# stm.net
KiCad netlist of a schematic drawn in Altium Designer
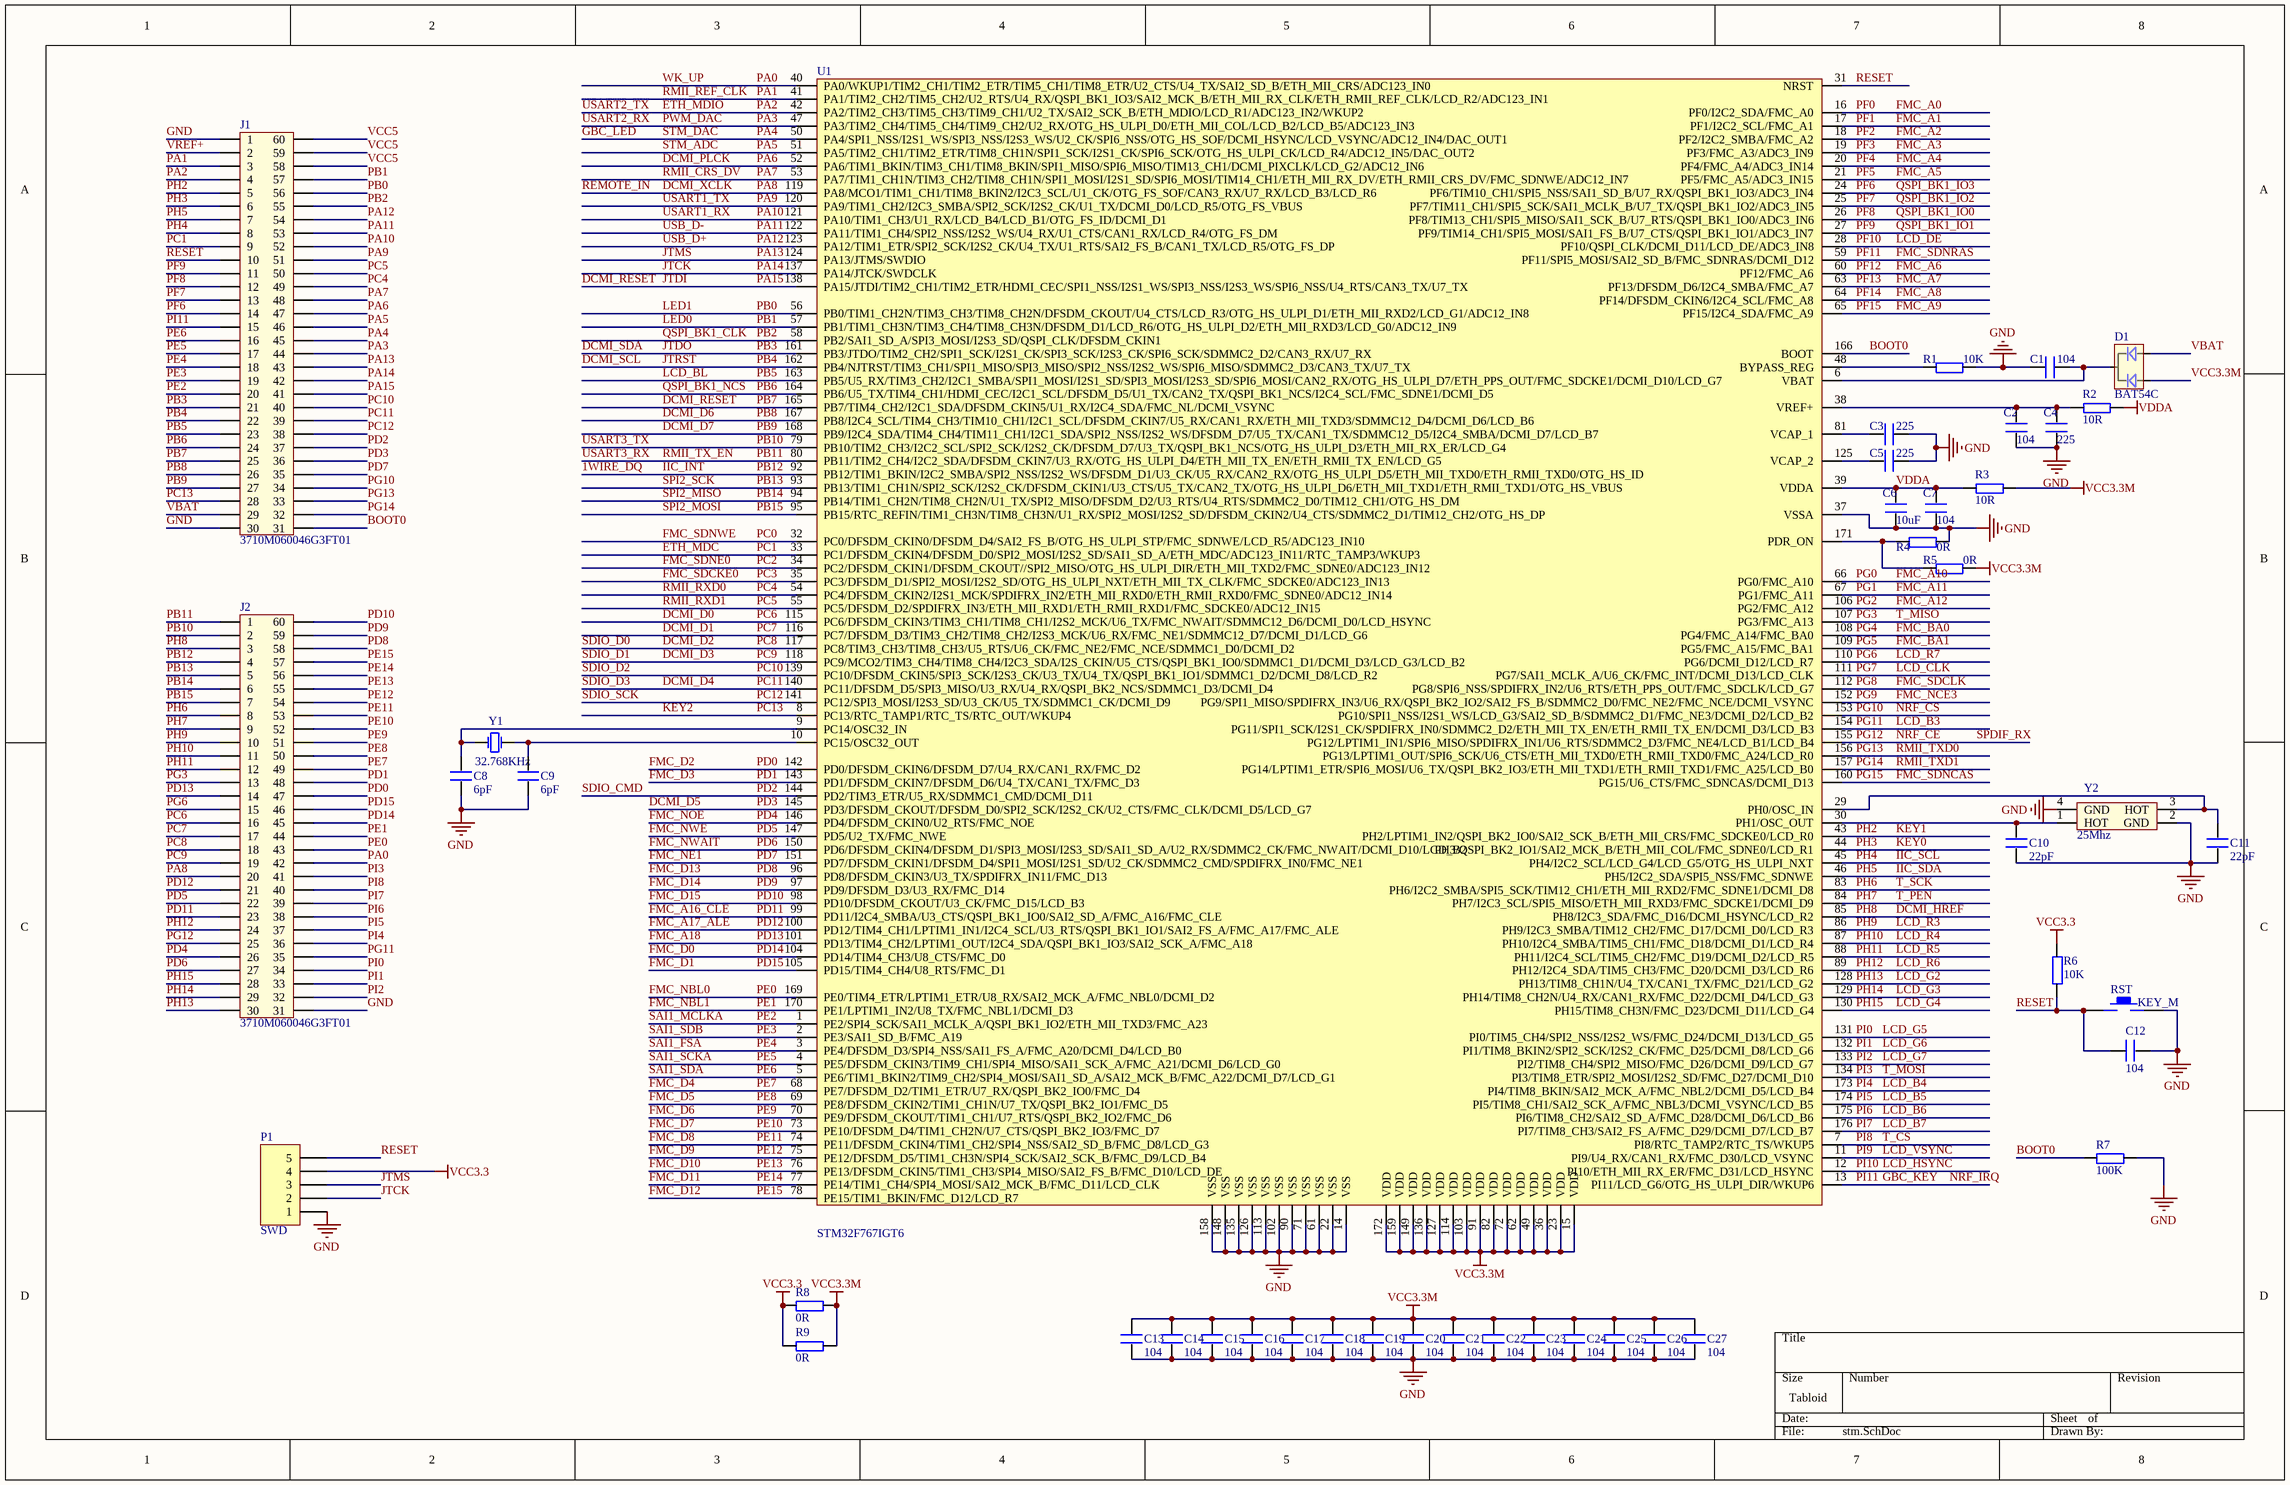
[diagram p0: stm.SchDoc]

(export (version "E")
  (design (tool "Eeschema 10.0.6"))
  (components
    (comp (ref "C1") (value "104") (footprint "0805") (libsource (lib "STM32F767核心板封装库") (part "C")))
    (comp (ref "C2") (value "104") (footprint "0805") (libsource (lib "STM32F767核心板封装库") (part "C")))
    (comp (ref "C3") (value "225") (footprint "0805") (libsource (lib "STM32F767核心板封装库") (part "C")))
    (comp (ref "C4") (value "225") (footprint "0805") (libsource (lib "STM32F767核心板封装库") (part "C")))
    (comp (ref "C5") (value "225") (footprint "0805") (libsource (lib "STM32F767核心板封装库") (part "C")))
    (comp (ref "C6") (value "10uF") (footprint "0805") (libsource (lib "STM32F767核心板封装库") (part "C")))
    (comp (ref "C7") (value "104") (footprint "0805") (libsource (lib "STM32F767核心板封装库") (part "C")))
    (comp (ref "C8") (value "6pF") (footprint "0805") (libsource (lib "STM32F767核心板封装库") (part "C")))
    (comp (ref "C9") (value "6pF") (footprint "0805") (libsource (lib "STM32F767核心板封装库") (part "C")))
    (comp (ref "C10") (value "22pF") (footprint "0805") (libsource (lib "STM32F767核心板封装库") (part "C")))
    (comp (ref "C11") (value "22pF") (footprint "0805") (libsource (lib "STM32F767核心板封装库") (part "C")))
    (comp (ref "C12") (value "104") (footprint "0805") (libsource (lib "STM32F767核心板封装库") (part "C")))
    (comp (ref "C13") (value "104") (footprint "0805") (libsource (lib "STM32F767核心板封装库") (part "C")))
    (comp (ref "C14") (value "104") (footprint "0805") (libsource (lib "STM32F767核心板封装库") (part "C")))
    (comp (ref "C15") (value "104") (footprint "0805") (libsource (lib "STM32F767核心板封装库") (part "C")))
    (comp (ref "C16") (value "104") (footprint "0805") (libsource (lib "STM32F767核心板封装库") (part "C")))
    (comp (ref "C17") (value "104") (footprint "0805") (libsource (lib "STM32F767核心板封装库") (part "C")))
    (comp (ref "C18") (value "104") (footprint "0805") (libsource (lib "STM32F767核心板封装库") (part "C")))
    (comp (ref "C19") (value "104") (footprint "0805") (libsource (lib "STM32F767核心板封装库") (part "C")))
    (comp (ref "C20") (value "104") (footprint "0805") (libsource (lib "STM32F767核心板封装库") (part "C")))
    (comp (ref "C21") (value "104") (footprint "0805") (libsource (lib "STM32F767核心板封装库") (part "C")))
    (comp (ref "C22") (value "104") (footprint "0805") (libsource (lib "STM32F767核心板封装库") (part "C")))
    (comp (ref "C23") (value "104") (footprint "0805") (libsource (lib "STM32F767核心板封装库") (part "C")))
    (comp (ref "C24") (value "104") (footprint "0805") (libsource (lib "STM32F767核心板封装库") (part "C")))
    (comp (ref "C25") (value "104") (footprint "0805") (libsource (lib "STM32F767核心板封装库") (part "C")))
    (comp (ref "C26") (value "104") (footprint "0805") (libsource (lib "STM32F767核心板封装库") (part "C")))
    (comp (ref "C27") (value "104") (footprint "0805") (libsource (lib "STM32F767核心板封装库") (part "C")))
    (comp (ref "D1")
      (value "BAT54C")
      (footprint "SOT-23")
      (description "双肖特基二极管")
      (libsource (lib "STM32F767核心板封装库") (part "BAT54C"))
    )
    (comp (ref "J1")
      (value "3710M060046G3FT01")
      (footprint "3710F060046G3FT01")
      (description "3710F060046G3FT01")
      (libsource (lib "STM32F767核心板封装库") (part "3710F"))
    )
    (comp (ref "J2")
      (value "3710M060046G3FT01")
      (footprint "3710F060046G3FT01")
      (description "3710F060046G3FT01")
      (libsource (lib "STM32F767核心板封装库") (part "3710F"))
    )
    (comp (ref "P1")
      (value "SWD")
      (footprint "HDR1X5")
      (description "Header, 5-Pin")
      (fields (field (name "PUBLISHER") "Altium Limited"))
      (libsource (lib "STM32F767核心板封装库") (part "Header 5"))
    )
    (comp (ref "R1") (value "10K") (footprint "0805") (libsource (lib "STM32F767核心板封装库") (part "R")))
    (comp (ref "R2") (value "10R") (footprint "0805") (libsource (lib "STM32F767核心板封装库") (part "R")))
    (comp (ref "R3") (value "10R") (footprint "0805") (libsource (lib "STM32F767核心板封装库") (part "R")))
    (comp (ref "R4") (value "0R") (footprint "0805") (libsource (lib "STM32F767核心板封装库") (part "R")))
    (comp (ref "R5") (value "0R") (footprint "0805") (libsource (lib "STM32F767核心板封装库") (part "R")))
    (comp (ref "R6") (value "10K") (footprint "0805") (libsource (lib "STM32F767核心板封装库") (part "R")))
    (comp (ref "R7") (value "100K") (footprint "0805") (libsource (lib "STM32F767核心板封装库") (part "R")))
    (comp (ref "R8") (value "0R") (footprint "0805") (libsource (lib "STM32F767核心板封装库") (part "R")))
    (comp (ref "R9") (value "0R") (footprint "0805") (libsource (lib "STM32F767核心板封装库") (part "R")))
    (comp (ref "RST")
      (value "KEY_M")
      (footprint "KEY_SOP3625")
      (libsource (lib "STM32F767核心板封装库") (part "KEY_M"))
    )
    (comp (ref "U1")
      (value "STM32F767IGT6")
      (footprint "LQFP176")
      (libsource (lib "STM32F767核心板封装库") (part "STM32F767IGT6"))
    )
    (comp (ref "Y1")
      (value "32.768KHz")
      (footprint "XTAL3215")
      (description "普通晶振")
      (fields (field (name "PUBLISHER") "Altium Limited"))
      (libsource (lib "STM32F767核心板封装库") (part "XTAL"))
    )
    (comp (ref "Y2")
      (value "25Mhz")
      (footprint "XTAL3225")
      (description "3225贴片无源晶振")
      (libsource (lib "STM32F767核心板封装库") (part "XTAL_3225"))
    )
  )
  (nets
    (net (code "1") (name "/1WIRE_DQ") (class "Default")
      (node (ref "J2") (pin "4") (pinfunction "4_4") (pintype "passive"))
      (node (ref "U1") (pin "92") (pinfunction "PB12/TIM1_BKIN/I2C2_SMBA/SPI2_NSS/I2S2_WS/DFSDM_D1/U3_CK/U5_RX/CAN2_RX/OTG_HS_ULPI_D5/ETH_MII_TXD0/ETH_RMII_TXD0/OTG_HS_ID_92") (pintype "passive"))
    )
    (net (code "2") (name "/BOOT0") (class "Default")
      (node (ref "J1") (pin "31") (pinfunction "31_31") (pintype "passive"))
      (node (ref "R7") (pin "1") (pintype "passive"))
      (node (ref "U1") (pin "166") (pinfunction "BOOT_166") (pintype "passive"))
    )
    (net (code "3") (name "/DCMI_D0") (class "Default")
      (node (ref "J2") (pin "16") (pinfunction "16_16") (pintype "passive"))
      (node (ref "U1") (pin "115") (pinfunction "PC6/DFSDM_CKIN3/TIM3_CH1/TIM8_CH1/I2S2_MCK/U6_TX/FMC_NWAIT/SDMMC12_D6/DCMI_D0/LCD_HSYNC_115") (pintype "passive"))
    )
    (net (code "4") (name "/DCMI_D1") (class "Default")
      (node (ref "J2") (pin "17") (pinfunction "17_17") (pintype "passive"))
      (node (ref "U1") (pin "116") (pinfunction "PC7/DFSDM_D3/TIM3_CH2/TIM8_CH2/I2S3_MCK/U6_RX/FMC_NE1/SDMMC12_D7/DCMI_D1/LCD_G6_116") (pintype "passive"))
    )
    (net (code "5") (name "/DCMI_D2") (class "Default")
      (node (ref "J2") (pin "18") (pinfunction "18_18") (pintype "passive"))
      (node (ref "U1") (pin "117") (pinfunction "PC8/TIM3_CH3/TIM8_CH3/U5_RTS/U6_CK/FMC_NE2/FMC_NCE/SDMMC1_D0/DCMI_D2_117") (pintype "passive"))
    )
    (net (code "6") (name "/DCMI_D3") (class "Default")
      (node (ref "J2") (pin "19") (pinfunction "19_19") (pintype "passive"))
      (node (ref "U1") (pin "118") (pinfunction "PC9/MCO2/TIM3_CH4/TIM8_CH4/I2C3_SDA/I2S_CKIN/U5_CTS/QSPI_BK1_IO0/SDMMC1_D1/DCMI_D3/LCD_G3/LCD_B2_118") (pintype "passive"))
    )
    (net (code "7") (name "/DCMI_D4") (class "Default")
      (node (ref "J1") (pin "39") (pinfunction "39_39") (pintype "passive"))
      (node (ref "U1") (pin "140") (pinfunction "PC11/DFSDM_D5/SPI3_MISO/U3_RX/U4_RX/QSPI_BK2_NCS/SDMMC1_D3/DCMI_D4_140") (pintype "passive"))
    )
    (net (code "8") (name "/DCMI_D5") (class "Default")
      (node (ref "J1") (pin "36") (pinfunction "36_36") (pintype "passive"))
      (node (ref "U1") (pin "145") (pinfunction "PD3/DFSDM_CKOUT/DFSDM_D0/SPI2_SCK/I2S2_CK/U2_CTS/FMC_CLK/DCMI_D5/LCD_G7_145") (pintype "passive"))
    )
    (net (code "9") (name "/DCMI_D6") (class "Default")
      (node (ref "J1") (pin "26") (pinfunction "26_26") (pintype "passive"))
      (node (ref "U1") (pin "167") (pinfunction "PB8/I2C4_SCL/TIM4_CH3/TIM10_CH1/I2C1_SCL/DFSDM_CKIN7/U5_RX/CAN1_RX/ETH_MII_TXD3/SDMMC12_D4/DCMI_D6/LCD_B6_167") (pintype "passive"))
    )
    (net (code "10") (name "/DCMI_D7") (class "Default")
      (node (ref "J1") (pin "27") (pinfunction "27_27") (pintype "passive"))
      (node (ref "U1") (pin "168") (pinfunction "PB9/I2C4_SDA/TIM4_CH4/TIM11_CH1/I2C1_SDA/SPI2_NSS/I2S2_WS/DFSDM_D7/U5_TX/CAN1_TX/SDMMC12_D5/I2C4_SMBA/DCMI_D7/LCD_B7_168") (pintype "passive"))
    )
    (net (code "11") (name "/DCMI_HREF") (class "Default")
      (node (ref "J2") (pin "3") (pinfunction "3_3") (pintype "passive"))
      (node (ref "U1") (pin "85") (pinfunction "PH8/I2C3_SDA/FMC_D16/DCMI_HSYNC/LCD_R2_85") (pintype "passive"))
    )
    (net (code "12") (name "/DCMI_PLCK") (class "Default")
      (node (ref "J1") (pin "47") (pinfunction "47_47") (pintype "passive"))
      (node (ref "U1") (pin "52") (pinfunction "PA6/TIM1_BKIN/TIM3_CH1/TIM8_BKIN/SPI1_MISO/SPI6_MISO/TIM13_CH1/DCMI_PIXCLK/LCD_G2/ADC12_IN6_52") (pintype "passive"))
    )
    (net (code "13") (name "/DCMI_RESET") (class "Default")
      (node (ref "J1") (pin "25") (pinfunction "25_25") (pintype "passive"))
      (node (ref "J1") (pin "41") (pinfunction "41_41") (pintype "passive"))
      (node (ref "U1") (pin "138") (pinfunction "PA15/JTDI/TIM2_CH1/TIM2_ETR/HDMI_CEC/SPI1_NSS/I2S1_WS/SPI3_NSS/I2S3_WS/SPI6_NSS/U4_RTS/CAN3_TX/U7_TX_138") (pintype "passive"))
      (node (ref "U1") (pin "165") (pinfunction "PB7/TIM4_CH2/I2C1_SDA/DFSDM_CKIN5/U1_RX/I2C4_SDA/FMC_NL/DCMI_VSYNC_165") (pintype "passive"))
    )
    (net (code "14") (name "/DCMI_SCL") (class "Default")
      (node (ref "J1") (pin "22") (pinfunction "22_22") (pintype "passive"))
      (node (ref "U1") (pin "162") (pinfunction "PB4/NJTRST/TIM3_CH1/SPI1_MISO/SPI3_MISO/SPI2_NSS/I2S2_WS/SPI6_MISO/SDMMC2_D3/CAN3_TX/U7_TX_162") (pintype "passive"))
    )
    (net (code "15") (name "/DCMI_SDA") (class "Default")
      (node (ref "J1") (pin "21") (pinfunction "21_21") (pintype "passive"))
      (node (ref "U1") (pin "161") (pinfunction "PB3/JTDO/TIM2_CH2/SPI1_SCK/I2S1_CK/SPI3_SCK/I2S3_CK/SPI6_SCK/SDMMC2_D2/CAN3_RX/U7_RX_161") (pintype "passive"))
    )
    (net (code "16") (name "/DCMI_XCLK") (class "Default")
      (node (ref "J2") (pin "20") (pinfunction "20_20") (pintype "passive"))
      (node (ref "U1") (pin "119") (pinfunction "PA8/MCO1/TIM1_CH1/TIM8_BKIN2/I2C3_SCL/U1_CK/OTG_FS_SOF/CAN3_RX/U7_RX/LCD_B3/LCD_R6_119") (pintype "passive"))
    )
    (net (code "17") (name "/ETH_MDC") (class "Default")
      (node (ref "J1") (pin "9") (pinfunction "9_9") (pintype "passive"))
      (node (ref "U1") (pin "33") (pinfunction "PC1/DFSDM_CKIN4/DFSDM_D0/SPI2_MOSI/I2S2_SD/SAI1_SD_A/ETH_MDC/ADC123_IN11/RTC_TAMP3/WKUP3_33") (pintype "passive"))
    )
    (net (code "18") (name "/ETH_MDIO") (class "Default")
      (node (ref "J1") (pin "4") (pinfunction "4_4") (pintype "passive"))
      (node (ref "U1") (pin "42") (pinfunction "PA2/TIM2_CH3/TIM5_CH3/TIM9_CH1/U2_TX/SAI2_SCK_B/ETH_MDIO/LCD_R1/ADC123_IN2/WKUP2_42") (pintype "passive"))
    )
    (net (code "19") (name "/FMC_A0") (class "Default")
      (node (ref "U1") (pin "16") (pinfunction "PF0/I2C2_SDA/FMC_A0_16") (pintype "passive"))
    )
    (net (code "20") (name "/FMC_A1") (class "Default")
      (node (ref "U1") (pin "17") (pinfunction "PF1/I2C2_SCL/FMC_A1_17") (pintype "passive"))
    )
    (net (code "21") (name "/FMC_A2") (class "Default")
      (node (ref "U1") (pin "18") (pinfunction "PF2/I2C2_SMBA/FMC_A2_18") (pintype "passive"))
    )
    (net (code "22") (name "/FMC_A3") (class "Default")
      (node (ref "U1") (pin "19") (pinfunction "PF3/FMC_A3/ADC3_IN9_19") (pintype "passive"))
    )
    (net (code "23") (name "/FMC_A4") (class "Default")
      (node (ref "U1") (pin "20") (pinfunction "PF4/FMC_A4/ADC3_IN14_20") (pintype "passive"))
    )
    (net (code "24") (name "/FMC_A5") (class "Default")
      (node (ref "U1") (pin "21") (pinfunction "PF5/FMC_A5/ADC3_IN15_21") (pintype "passive"))
    )
    (net (code "25") (name "/FMC_A6") (class "Default")
      (node (ref "U1") (pin "60") (pinfunction "PF12/FMC_A6_60") (pintype "passive"))
    )
    (net (code "26") (name "/FMC_A7") (class "Default")
      (node (ref "U1") (pin "63") (pinfunction "PF13/DFSDM_D6/I2C4_SMBA/FMC_A7_63") (pintype "passive"))
    )
    (net (code "27") (name "/FMC_A8") (class "Default")
      (node (ref "U1") (pin "64") (pinfunction "PF14/DFSDM_CKIN6/I2C4_SCL/FMC_A8_64") (pintype "passive"))
    )
    (net (code "28") (name "/FMC_A9") (class "Default")
      (node (ref "U1") (pin "65") (pinfunction "PF15/I2C4_SDA/FMC_A9_65") (pintype "passive"))
    )
    (net (code "29") (name "/FMC_A10") (class "Default")
      (node (ref "U1") (pin "66") (pinfunction "PG0/FMC_A10_66") (pintype "passive"))
    )
    (net (code "30") (name "/FMC_A11") (class "Default")
      (node (ref "U1") (pin "67") (pinfunction "PG1/FMC_A11_67") (pintype "passive"))
    )
    (net (code "31") (name "/FMC_A12") (class "Default")
      (node (ref "U1") (pin "106") (pinfunction "PG2/FMC_A12_106") (pintype "passive"))
    )
    (net (code "32") (name "/FMC_A16_CLE") (class "Default")
      (node (ref "J2") (pin "23") (pinfunction "23_23") (pintype "passive"))
      (node (ref "U1") (pin "99") (pinfunction "PD11/I2C4_SMBA/U3_CTS/QSPI_BK1_IO0/SAI2_SD_A/FMC_A16/FMC_CLE_99") (pintype "passive"))
    )
    (net (code "33") (name "/FMC_A17_ALE") (class "Default")
      (node (ref "J2") (pin "21") (pinfunction "21_21") (pintype "passive"))
      (node (ref "U1") (pin "100") (pinfunction "PD12/TIM4_CH1/LPTIM1_IN1/I2C4_SCL/U3_RTS/QSPI_BK1_IO1/SAI2_FS_A/FMC_A17/FMC_ALE_100") (pintype "passive"))
    )
    (net (code "34") (name "/FMC_A18") (class "Default")
      (node (ref "J2") (pin "14") (pinfunction "14_14") (pintype "passive"))
      (node (ref "U1") (pin "101") (pinfunction "PD13/TIM4_CH2/LPTIM1_OUT/I2C4_SDA/QSPI_BK1_IO3/SAI2_SCK_A/FMC_A18_101") (pintype "passive"))
    )
    (net (code "35") (name "/FMC_BA0") (class "Default")
      (node (ref "U1") (pin "108") (pinfunction "PG4/FMC_A14/FMC_BA0_108") (pintype "passive"))
    )
    (net (code "36") (name "/FMC_BA1") (class "Default")
      (node (ref "U1") (pin "109") (pinfunction "PG5/FMC_A15/FMC_BA1_109") (pintype "passive"))
    )
    (net (code "37") (name "/FMC_D0") (class "Default")
      (node (ref "J2") (pin "45") (pinfunction "45_45") (pintype "passive"))
      (node (ref "U1") (pin "104") (pinfunction "PD14/TIM4_CH3/U8_CTS/FMC_D0_104") (pintype "passive"))
    )
    (net (code "38") (name "/FMC_D1") (class "Default")
      (node (ref "J2") (pin "46") (pinfunction "46_46") (pintype "passive"))
      (node (ref "U1") (pin "105") (pinfunction "PD15/TIM4_CH4/U8_RTS/FMC_D1_105") (pintype "passive"))
    )
    (net (code "39") (name "/FMC_D2") (class "Default")
      (node (ref "J2") (pin "47") (pinfunction "47_47") (pintype "passive"))
      (node (ref "U1") (pin "142") (pinfunction "PD0/DFSDM_CKIN6/DFSDM_D7/U4_RX/CAN1_RX/FMC_D2_142") (pintype "passive"))
    )
    (net (code "40") (name "/FMC_D3") (class "Default")
      (node (ref "J2") (pin "48") (pinfunction "48_48") (pintype "passive"))
      (node (ref "U1") (pin "143") (pinfunction "PD1/DFSDM_CKIN7/DFSDM_D6/U4_TX/CAN1_TX/FMC_D3_143") (pintype "passive"))
    )
    (net (code "41") (name "/FMC_D4") (class "Default")
      (node (ref "J2") (pin "49") (pinfunction "49_49") (pintype "passive"))
      (node (ref "U1") (pin "68") (pinfunction "PE7/DFSDM_D2/TIM1_ETR/U7_RX/QSPI_BK2_IO0/FMC_D4_68") (pintype "passive"))
    )
    (net (code "42") (name "/FMC_D5") (class "Default")
      (node (ref "J2") (pin "50") (pinfunction "50_50") (pintype "passive"))
      (node (ref "U1") (pin "69") (pinfunction "PE8/DFSDM_CKIN2/TIM1_CH1N/U7_TX/QSPI_BK2_IO1/FMC_D5_69") (pintype "passive"))
    )
    (net (code "43") (name "/FMC_D6") (class "Default")
      (node (ref "J2") (pin "51") (pinfunction "51_51") (pintype "passive"))
      (node (ref "U1") (pin "70") (pinfunction "PE9/DFSDM_CKOUT/TIM1_CH1/U7_RTS/QSPI_BK2_IO2/FMC_D6_70") (pintype "passive"))
    )
    (net (code "44") (name "/FMC_D7") (class "Default")
      (node (ref "J2") (pin "52") (pinfunction "52_52") (pintype "passive"))
      (node (ref "U1") (pin "73") (pinfunction "PE10/DFSDM_D4/TIM1_CH2N/U7_CTS/QSPI_BK2_IO3/FMC_D7_73") (pintype "passive"))
    )
    (net (code "45") (name "/FMC_D8") (class "Default")
      (node (ref "J2") (pin "53") (pinfunction "53_53") (pintype "passive"))
      (node (ref "U1") (pin "74") (pinfunction "PE11/DFSDM_CKIN4/TIM1_CH2/SPI4_NSS/SAI2_SD_B/FMC_D8/LCD_G3_74") (pintype "passive"))
    )
    (net (code "46") (name "/FMC_D9") (class "Default")
      (node (ref "J2") (pin "54") (pinfunction "54_54") (pintype "passive"))
      (node (ref "U1") (pin "75") (pinfunction "PE12/DFSDM_D5/TIM1_CH3N/SPI4_SCK/SAI2_SCK_B/FMC_D9/LCD_B4_75") (pintype "passive"))
    )
    (net (code "47") (name "/FMC_D10") (class "Default")
      (node (ref "J2") (pin "55") (pinfunction "55_55") (pintype "passive"))
      (node (ref "U1") (pin "76") (pinfunction "PE13/DFSDM_CKIN5/TIM1_CH3/SPI4_MISO/SAI2_FS_B/FMC_D10/LCD_DE_76") (pintype "passive"))
    )
    (net (code "48") (name "/FMC_D11") (class "Default")
      (node (ref "J2") (pin "56") (pinfunction "56_56") (pintype "passive"))
      (node (ref "U1") (pin "77") (pinfunction "PE14/TIM1_CH4/SPI4_MOSI/SAI2_MCK_B/FMC_D11/LCD_CLK_77") (pintype "passive"))
    )
    (net (code "49") (name "/FMC_D12") (class "Default")
      (node (ref "J2") (pin "57") (pinfunction "57_57") (pintype "passive"))
      (node (ref "U1") (pin "78") (pinfunction "PE15/TIM1_BKIN/FMC_D12/LCD_R7_78") (pintype "passive"))
    )
    (net (code "50") (name "/FMC_D13") (class "Default")
      (node (ref "J2") (pin "58") (pinfunction "58_58") (pintype "passive"))
      (node (ref "U1") (pin "96") (pinfunction "PD8/DFSDM_CKIN3/U3_TX/SPDIFRX_IN11/FMC_D13_96") (pintype "passive"))
    )
    (net (code "51") (name "/FMC_D14") (class "Default")
      (node (ref "J2") (pin "59") (pinfunction "59_59") (pintype "passive"))
      (node (ref "U1") (pin "97") (pinfunction "PD9/DFSDM_D3/U3_RX/FMC_D14_97") (pintype "passive"))
    )
    (net (code "52") (name "/FMC_D15") (class "Default")
      (node (ref "J2") (pin "60") (pinfunction "60_60") (pintype "passive"))
      (node (ref "U1") (pin "98") (pinfunction "PD10/DFSDM_CKOUT/U3_CK/FMC_D15/LCD_B3_98") (pintype "passive"))
    )
    (net (code "53") (name "/FMC_NBL0") (class "Default")
      (node (ref "J2") (pin "43") (pinfunction "43_43") (pintype "passive"))
      (node (ref "U1") (pin "169") (pinfunction "PE0/TIM4_ETR/LPTIM1_ETR/U8_RX/SAI2_MCK_A/FMC_NBL0/DCMI_D2_169") (pintype "passive"))
    )
    (net (code "54") (name "/FMC_NBL1") (class "Default")
      (node (ref "J2") (pin "44") (pinfunction "44_44") (pintype "passive"))
      (node (ref "U1") (pin "170") (pinfunction "PE1/LPTIM1_IN2/U8_TX/FMC_NBL1/DCMI_D3_170") (pintype "passive"))
    )
    (net (code "55") (name "/FMC_NCE3") (class "Default")
      (node (ref "U1") (pin "152") (pinfunction "PG9/SPI1_MISO/SPDIFRX_IN3/U6_RX/QSPI_BK2_IO2/SAI2_FS_B/SDMMC2_D0/FMC_NE2/FMC_NCE/DCMI_VSYNC_152") (pintype "passive"))
    )
    (net (code "56") (name "/FMC_NE1") (class "Default")
      (node (ref "J1") (pin "35") (pinfunction "35_35") (pintype "passive"))
      (node (ref "U1") (pin "151") (pinfunction "PD7/DFSDM_CKIN1/DFSDM_D4/SPI1_MOSI/I2S1_SD/U2_CK/SDMMC2_CMD/SPDIFRX_IN0/FMC_NE1_151") (pintype "passive"))
    )
    (net (code "57") (name "/FMC_NOE") (class "Default")
      (node (ref "J2") (pin "26") (pinfunction "26_26") (pintype "passive"))
      (node (ref "U1") (pin "146") (pinfunction "PD4/DFSDM_CKIN0/U2_RTS/FMC_NOE_146") (pintype "passive"))
    )
    (net (code "58") (name "/FMC_NWAIT") (class "Default")
      (node (ref "J2") (pin "27") (pinfunction "27_27") (pintype "passive"))
      (node (ref "U1") (pin "150") (pinfunction "PD6/DFSDM_CKIN4/DFSDM_D1/SPI3_MOSI/I2S3_SD/SAI1_SD_A/U2_RX/SDMMC2_CK/FMC_NWAIT/DCMI_D10/LCD_B2_150") (pintype "passive"))
    )
    (net (code "59") (name "/FMC_NWE") (class "Default")
      (node (ref "J2") (pin "22") (pinfunction "22_22") (pintype "passive"))
      (node (ref "U1") (pin "147") (pinfunction "PD5/U2_TX/FMC_NWE_147") (pintype "passive"))
    )
    (net (code "60") (name "/FMC_SDCKE0") (class "Default")
      (node (ref "U1") (pin "35") (pinfunction "PC3/DFSDM_D1/SPI2_MOSI/I2S2_SD/OTG_HS_ULPI_NXT/ETH_MII_TX_CLK/FMC_SDCKE0/ADC123_IN13_35") (pintype "passive"))
    )
    (net (code "61") (name "/FMC_SDCLK") (class "Default")
      (node (ref "U1") (pin "112") (pinfunction "PG8/SPI6_NSS/SPDIFRX_IN2/U6_RTS/ETH_PPS_OUT/FMC_SDCLK/LCD_G7_112") (pintype "passive"))
    )
    (net (code "62") (name "/FMC_SDNCAS") (class "Default")
      (node (ref "U1") (pin "160") (pinfunction "PG15/U6_CTS/FMC_SDNCAS/DCMI_D13_160") (pintype "passive"))
    )
    (net (code "63") (name "/FMC_SDNE0") (class "Default")
      (node (ref "U1") (pin "34") (pinfunction "PC2/DFSDM_CKIN1/DFSDM_CKOUT//SPI2_MISO/OTG_HS_ULPI_DIR/ETH_MII_TXD2/FMC_SDNE0/ADC123_IN12_34") (pintype "passive"))
    )
    (net (code "64") (name "/FMC_SDNRAS") (class "Default")
      (node (ref "U1") (pin "59") (pinfunction "PF11/SPI5_MOSI/SAI2_SD_B/FMC_SDNRAS/DCMI_D12_59") (pintype "passive"))
    )
    (net (code "65") (name "/FMC_SDNWE") (class "Default")
      (node (ref "U1") (pin "32") (pinfunction "PC0/DFSDM_CKIN0/DFSDM_D4/SAI2_FS_B/OTG_HS_ULPI_STP/FMC_SDNWE/LCD_R5/ADC123_IN10_32") (pintype "passive"))
    )
    (net (code "66") (name "/GBC_KEY") (class "Default")
      (node (ref "J1") (pin "15") (pinfunction "15_15") (pintype "passive"))
      (node (ref "U1") (pin "13") (pinfunction "PI11/LCD_G6/OTG_HS_ULPI_DIR/WKUP6_13") (pintype "passive"))
    )
    (net (code "67") (name "/GBC_LED") (class "Default")
      (node (ref "J1") (pin "45") (pinfunction "45_45") (pintype "passive"))
      (node (ref "U1") (pin "50") (pinfunction "PA4/SPI1_NSS/I2S1_WS/SPI3_NSS/I2S3_WS/U2_CK/SPI6_NSS/OTG_HS_SOF/DCMI_HSYNC/LCD_VSYNC/ADC12_IN4/DAC_OUT1_50") (pintype "passive"))
    )
    (net (code "68") (name "/IIC_SCL") (class "Default")
      (node (ref "J1") (pin "8") (pinfunction "8_8") (pintype "passive"))
      (node (ref "U1") (pin "45") (pinfunction "PH4/I2C2_SCL/LCD_G4/LCD_G5/OTG_HS_ULPI_NXT_45") (pintype "passive"))
    )
    (net (code "69") (name "/IIC_SDA") (class "Default")
      (node (ref "J1") (pin "7") (pinfunction "7_7") (pintype "passive"))
      (node (ref "U1") (pin "46") (pinfunction "PH5/I2C2_SDA/SPI5_NSS/FMC_SDNWE_46") (pintype "passive"))
    )
    (net (code "70") (name "/JTCK") (class "Default")
      (node (ref "J1") (pin "42") (pinfunction "42_42") (pintype "passive"))
      (node (ref "P1") (pin "2") (pinfunction "2_2") (pintype "passive"))
      (node (ref "U1") (pin "137") (pinfunction "PA14/JTCK/SWDCLK_137") (pintype "passive"))
    )
    (net (code "71") (name "/JTMS") (class "Default")
      (node (ref "J1") (pin "43") (pinfunction "43_43") (pintype "passive"))
      (node (ref "P1") (pin "3") (pinfunction "3_3") (pintype "passive"))
      (node (ref "U1") (pin "124") (pinfunction "PA13/JTMS/SWDIO_124") (pintype "passive"))
    )
    (net (code "72") (name "/KEY0") (class "Default")
      (node (ref "J1") (pin "6") (pinfunction "6_6") (pintype "passive"))
      (node (ref "U1") (pin "44") (pinfunction "PH3/QSPI_BK2_IO1/SAI2_MCK_B/ETH_MII_COL/FMC_SDNE0/LCD_R1_44") (pintype "passive"))
    )
    (net (code "73") (name "/KEY1") (class "Default")
      (node (ref "J1") (pin "5") (pinfunction "5_5") (pintype "passive"))
      (node (ref "U1") (pin "43") (pinfunction "PH2/LPTIM1_IN2/QSPI_BK2_IO0/SAI2_SCK_B/ETH_MII_CRS/FMC_SDCKE0/LCD_R0_43") (pintype "passive"))
    )
    (net (code "74") (name "/KEY2") (class "Default")
      (node (ref "J1") (pin "28") (pinfunction "28_28") (pintype "passive"))
      (node (ref "U1") (pin "8") (pinfunction "PC13/RTC_TAMP1/RTC_TS/RTC_OUT/WKUP4_8") (pintype "passive"))
    )
    (net (code "75") (name "/LCD_B3") (class "Default")
      (node (ref "J2") (pin "35") (pinfunction "35_35") (pintype "passive"))
      (node (ref "U1") (pin "154") (pinfunction "PG11/SPI1_SCK/I2S1_CK/SPDIFRX_IN0/SDMMC2_D2/ETH_MII_TX_EN/ETH_RMII_TX_EN/DCMI_D3/LCD_B3_154") (pintype "passive"))
    )
    (net (code "76") (name "/LCD_B4") (class "Default")
      (node (ref "J2") (pin "36") (pinfunction "36_36") (pintype "passive"))
      (node (ref "U1") (pin "173") (pinfunction "PI4/TIM8_BKIN/SAI2_MCK_A/FMC_NBL2/DCMI_D5/LCD_B4_173") (pintype "passive"))
    )
    (net (code "77") (name "/LCD_B5") (class "Default")
      (node (ref "J2") (pin "37") (pinfunction "37_37") (pintype "passive"))
      (node (ref "U1") (pin "174") (pinfunction "PI5/TIM8_CH1/SAI2_SCK_A/FMC_NBL3/DCMI_VSYNC/LCD_B5_174") (pintype "passive"))
    )
    (net (code "78") (name "/LCD_B6") (class "Default")
      (node (ref "J2") (pin "38") (pinfunction "38_38") (pintype "passive"))
      (node (ref "U1") (pin "175") (pinfunction "PI6/TIM8_CH2/SAI2_SD_A/FMC_D28/DCMI_D6/LCD_B6_175") (pintype "passive"))
    )
    (net (code "79") (name "/LCD_B7") (class "Default")
      (node (ref "J2") (pin "39") (pinfunction "39_39") (pintype "passive"))
      (node (ref "U1") (pin "176") (pinfunction "PI7/TIM8_CH3/SAI2_FS_A/FMC_D29/DCMI_D7/LCD_B7_176") (pintype "passive"))
    )
    (net (code "80") (name "/LCD_BL") (class "Default")
      (node (ref "J1") (pin "23") (pinfunction "23_23") (pintype "passive"))
      (node (ref "U1") (pin "163") (pinfunction "PB5/U5_RX/TIM3_CH2/I2C1_SMBA/SPI1_MOSI/I2S1_SD/SPI3_MOSI/I2S3_SD/SPI6_MOSI/CAN2_RX/OTG_HS_ULPI_D7/ETH_PPS_OUT/FMC_SDCKE1/DCMI_D10/LCD_G7_163") (pintype "passive"))
    )
    (net (code "81") (name "/LCD_CLK") (class "Default")
      (node (ref "U1") (pin "111") (pinfunction "PG7/SAI1_MCLK_A/U6_CK/FMC_INT/DCMI_D13/LCD_CLK_111") (pintype "passive"))
    )
    (net (code "82") (name "/LCD_DE") (class "Default")
      (node (ref "U1") (pin "28") (pinfunction "PF10/QSPI_CLK/DCMI_D11/LCD_DE/ADC3_IN8_28") (pintype "passive"))
    )
    (net (code "83") (name "/LCD_G2") (class "Default")
      (node (ref "J2") (pin "30") (pinfunction "30_30") (pintype "passive"))
      (node (ref "U1") (pin "128") (pinfunction "PH13/TIM8_CH1N/U4_TX/CAN1_TX/FMC_D21/LCD_G2_128") (pintype "passive"))
    )
    (net (code "84") (name "/LCD_G3") (class "Default")
      (node (ref "J2") (pin "29") (pinfunction "29_29") (pintype "passive"))
      (node (ref "U1") (pin "129") (pinfunction "PH14/TIM8_CH2N/U4_RX/CAN1_RX/FMC_D22/DCMI_D4/LCD_G3_129") (pintype "passive"))
    )
    (net (code "85") (name "/LCD_G4") (class "Default")
      (node (ref "J2") (pin "28") (pinfunction "28_28") (pintype "passive"))
      (node (ref "U1") (pin "130") (pinfunction "PH15/TIM8_CH3N/FMC_D23/DCMI_D11/LCD_G4_130") (pintype "passive"))
    )
    (net (code "86") (name "/LCD_G5") (class "Default")
      (node (ref "J2") (pin "34") (pinfunction "34_34") (pintype "passive"))
      (node (ref "U1") (pin "131") (pinfunction "PI0/TIM5_CH4/SPI2_NSS/I2S2_WS/FMC_D24/DCMI_D13/LCD_G5_131") (pintype "passive"))
    )
    (net (code "87") (name "/LCD_G6") (class "Default")
      (node (ref "J2") (pin "33") (pinfunction "33_33") (pintype "passive"))
      (node (ref "U1") (pin "132") (pinfunction "PI1/TIM8_BKIN2/SPI2_SCK/I2S2_CK/FMC_D25/DCMI_D8/LCD_G6_132") (pintype "passive"))
    )
    (net (code "88") (name "/LCD_G7") (class "Default")
      (node (ref "J2") (pin "32") (pinfunction "32_32") (pintype "passive"))
      (node (ref "U1") (pin "133") (pinfunction "PI2/TIM8_CH4/SPI2_MISO/FMC_D26/DCMI_D9/LCD_G7_133") (pintype "passive"))
    )
    (net (code "89") (name "/LCD_HSYNC") (class "Default")
      (node (ref "U1") (pin "12") (pinfunction "PI10/ETH_MII_RX_ER/FMC_D31/LCD_HSYNC_12") (pintype "passive"))
    )
    (net (code "90") (name "/LCD_R3") (class "Default")
      (node (ref "J2") (pin "10") (pinfunction "10_10") (pintype "passive"))
      (node (ref "U1") (pin "86") (pinfunction "PH9/I2C3_SMBA/TIM12_CH2/FMC_D17/DCMI_D0/LCD_R3_86") (pintype "passive"))
    )
    (net (code "91") (name "/LCD_R4") (class "Default")
      (node (ref "J2") (pin "11") (pinfunction "11_11") (pintype "passive"))
      (node (ref "U1") (pin "87") (pinfunction "PH10/I2C4_SMBA/TIM5_CH1/FMC_D18/DCMI_D1/LCD_R4_87") (pintype "passive"))
    )
    (net (code "92") (name "/LCD_R5") (class "Default")
      (node (ref "J2") (pin "12") (pinfunction "12_12") (pintype "passive"))
      (node (ref "U1") (pin "88") (pinfunction "PH11/I2C4_SCL/TIM5_CH2/FMC_D19/DCMI_D2/LCD_R5_88") (pintype "passive"))
    )
    (net (code "93") (name "/LCD_R6") (class "Default")
      (node (ref "J2") (pin "24") (pinfunction "24_24") (pintype "passive"))
      (node (ref "U1") (pin "89") (pinfunction "PH12/I2C4_SDA/TIM5_CH3/FMC_D20/DCMI_D3/LCD_R6_89") (pintype "passive"))
    )
    (net (code "94") (name "/LCD_R7") (class "Default")
      (node (ref "J2") (pin "15") (pinfunction "15_15") (pintype "passive"))
      (node (ref "U1") (pin "110") (pinfunction "PG6/DCMI_D12/LCD_R7_110") (pintype "passive"))
    )
    (net (code "95") (name "/LCD_VSYNC") (class "Default")
      (node (ref "U1") (pin "11") (pinfunction "PI9/U4_RX/CAN1_RX/FMC_D30/LCD_VSYNC_11") (pintype "passive"))
    )
    (net (code "96") (name "/LED0") (class "Default")
      (node (ref "J1") (pin "57") (pinfunction "57_57") (pintype "passive"))
      (node (ref "U1") (pin "57") (pinfunction "PB1/TIM1_CH3N/TIM3_CH4/TIM8_CH3N/DFSDM_D1/LCD_R6/OTG_HS_ULPI_D2/ETH_MII_RXD3/LCD_G0/ADC12_IN9_57") (pintype "passive"))
    )
    (net (code "97") (name "/LED1") (class "Default")
      (node (ref "J1") (pin "56") (pinfunction "56_56") (pintype "passive"))
      (node (ref "U1") (pin "56") (pinfunction "PB0/TIM1_CH2N/TIM3_CH3/TIM8_CH2N/DFSDM_CKOUT/U4_CTS/LCD_R3/OTG_HS_ULPI_D1/ETH_MII_RXD2/LCD_G1/ADC12_IN8_56") (pintype "passive"))
    )
    (net (code "98") (name "/NRF_CE") (class "Default")
      (node (ref "J2") (pin "25") (pinfunction "25_25") (pintype "passive"))
      (node (ref "U1") (pin "155") (pinfunction "PG12/LPTIM1_IN1/SPI6_MISO/SPDIFRX_IN1/U6_RTS/SDMMC2_D3/FMC_NE4/LCD_B1/LCD_B4_155") (pintype "passive"))
    )
    (net (code "99") (name "/NRF_CS") (class "Default")
      (node (ref "J1") (pin "34") (pinfunction "34_34") (pintype "passive"))
      (node (ref "U1") (pin "153") (pinfunction "PG10/SPI1_NSS/I2S1_WS/LCD_G3/SAI2_SD_B/SDMMC2_D1/FMC_NE3/DCMI_D2/LCD_B2_153") (pintype "passive"))
    )
    (net (code "100") (name "/PA0") (class "Default")
      (node (ref "J2") (pin "42") (pinfunction "42_42") (pintype "passive"))
      (node (ref "U1") (pin "40") (pinfunction "PA0/WKUP1/TIM2_CH1/TIM2_ETR/TIM5_CH1/TIM8_ETR/U2_CTS/U4_TX/SAI2_SD_B/ETH_MII_CRS/ADC123_IN0_40") (pintype "passive"))
    )
    (net (code "101") (name "/PA1") (class "Default")
      (node (ref "J1") (pin "3") (pinfunction "3_3") (pintype "passive"))
      (node (ref "U1") (pin "41") (pinfunction "PA1/TIM2_CH2/TIM5_CH2/U2_RTS/U4_RX/QSPI_BK1_IO3/SAI2_MCK_B/ETH_MII_RX_CLK/ETH_RMII_REF_CLK/LCD_R2/ADC123_IN1_41") (pintype "passive"))
    )
    (net (code "102") (name "/PA3") (class "Default")
      (node (ref "J1") (pin "44") (pinfunction "44_44") (pintype "passive"))
      (node (ref "U1") (pin "47") (pinfunction "PA3/TIM2_CH4/TIM5_CH4/TIM9_CH2/U2_RX/OTG_HS_ULPI_D0/ETH_MII_COL/LCD_B2/LCD_B5/ADC123_IN3_47") (pintype "passive"))
    )
    (net (code "103") (name "/PA5") (class "Default")
      (node (ref "J1") (pin "46") (pinfunction "46_46") (pintype "passive"))
      (node (ref "U1") (pin "51") (pinfunction "PA5/TIM2_CH1/TIM2_ETR/TIM8_CH1N/SPI1_SCK/I2S1_CK/SPI6_SCK/OTG_HS_ULPI_CK/LCD_R4/ADC12_IN5/DAC_OUT2_51") (pintype "passive"))
    )
    (net (code "104") (name "/PA7") (class "Default")
      (node (ref "J1") (pin "48") (pinfunction "48_48") (pintype "passive"))
      (node (ref "U1") (pin "53") (pinfunction "PA7/TIM1_CH1N/TIM3_CH2/TIM8_CH1N/SPI1_MOSI/I2S1_SD/SPI6_MOSI/TIM14_CH1/ETH_MII_RX_DV/ETH_RMII_CRS_DV/FMC_SDNWE/ADC12_IN7_53") (pintype "passive"))
    )
    (net (code "105") (name "/PA9") (class "Default")
      (node (ref "J1") (pin "51") (pinfunction "51_51") (pintype "passive"))
      (node (ref "U1") (pin "120") (pinfunction "PA9/TIM1_CH2/I2C3_SMBA/SPI2_SCK/I2S2_CK/U1_TX/DCMI_D0/LCD_R5/OTG_FS_VBUS_120") (pintype "passive"))
    )
    (net (code "106") (name "/PA10") (class "Default")
      (node (ref "J1") (pin "52") (pinfunction "52_52") (pintype "passive"))
      (node (ref "U1") (pin "121") (pinfunction "PA10/TIM1_CH3/U1_RX/LCD_B4/LCD_B1/OTG_FS_ID/DCMI_D1_121") (pintype "passive"))
    )
    (net (code "107") (name "/PA11") (class "Default")
      (node (ref "J1") (pin "53") (pinfunction "53_53") (pintype "passive"))
      (node (ref "U1") (pin "122") (pinfunction "PA11/TIM1_CH4/SPI2_NSS/I2S2_WS/U4_RX/U1_CTS/CAN1_RX/LCD_R4/OTG_FS_DM_122") (pintype "passive"))
    )
    (net (code "108") (name "/PA12") (class "Default")
      (node (ref "J1") (pin "54") (pinfunction "54_54") (pintype "passive"))
      (node (ref "U1") (pin "123") (pinfunction "PA12/TIM1_ETR/SPI2_SCK/I2S2_CK/U4_TX/U1_RTS/SAI2_FS_B/CAN1_TX/LCD_R5/OTG_FS_DP_123") (pintype "passive"))
    )
    (net (code "109") (name "/PB2") (class "Default")
      (node (ref "J1") (pin "55") (pinfunction "55_55") (pintype "passive"))
      (node (ref "U1") (pin "58") (pinfunction "PB2/SAI1_SD_A/SPI3_MOSI/I2S3_SD/QSPI_CLK/DFSDM_CKIN1_58") (pintype "passive"))
    )
    (net (code "110") (name "/PB6") (class "Default")
      (node (ref "J1") (pin "24") (pinfunction "24_24") (pintype "passive"))
      (node (ref "U1") (pin "164") (pinfunction "PB6/U5_TX/TIM4_CH1/HDMI_CEC/I2C1_SCL/DFSDM_D5/U1_TX/CAN2_TX/QSPI_BK1_NCS/I2C4_SCL/FMC_SDNE1/DCMI_D5_164") (pintype "passive"))
    )
    (net (code "111") (name "/PB10") (class "Default")
      (node (ref "J2") (pin "2") (pinfunction "2_2") (pintype "passive"))
      (node (ref "U1") (pin "79") (pinfunction "PB10/TIM2_CH3/I2C2_SCL/SPI2_SCK/I2S2_CK/DFSDM_D7/U3_TX/QSPI_BK1_NCS/OTG_HS_ULPI_D3/ETH_MII_RX_ER/LCD_G4_79") (pintype "passive"))
    )
    (net (code "112") (name "/PB11") (class "Default")
      (node (ref "J2") (pin "1") (pinfunction "1_1") (pintype "passive"))
      (node (ref "U1") (pin "80") (pinfunction "PB11/TIM2_CH4/I2C2_SDA/DFSDM_CKIN7/U3_RX/OTG_HS_ULPI_D4/ETH_MII_TX_EN/ETH_RMII_TX_EN/LCD_G5_80") (pintype "passive"))
    )
    (net (code "113") (name "/PB13") (class "Default")
      (node (ref "J2") (pin "5") (pinfunction "5_5") (pintype "passive"))
      (node (ref "U1") (pin "93") (pinfunction "PB13/TIM1_CH1N/SPI2_SCK/I2S2_CK/DFSDM_CKIN1/U3_CTS/U5_TX/CAN2_TX/OTG_HS_ULPI_D6/ETH_MII_TXD1/ETH_RMII_TXD1/OTG_HS_VBUS_93") (pintype "passive"))
    )
    (net (code "114") (name "/PB14") (class "Default")
      (node (ref "J2") (pin "6") (pinfunction "6_6") (pintype "passive"))
      (node (ref "U1") (pin "94") (pinfunction "PB14/TIM1_CH2N/TIM8_CH2N/U1_TX/SPI2_MISO/DFSDM_D2/U3_RTS/U4_RTS/SDMMC2_D0/TIM12_CH1/OTG_HS_DM_94") (pintype "passive"))
    )
    (net (code "115") (name "/PB15") (class "Default")
      (node (ref "J2") (pin "7") (pinfunction "7_7") (pintype "passive"))
      (node (ref "U1") (pin "95") (pinfunction "PB15/RTC_REFIN/TIM1_CH3N/TIM8_CH3N/U1_RX/SPI2_MOSI/I2S2_SD/DFSDM_CKIN2/U4_CTS/SDMMC2_D1/TIM12_CH2/OTG_HS_DP_95") (pintype "passive"))
    )
    (net (code "116") (name "/PC4") (class "Default")
      (node (ref "J1") (pin "49") (pinfunction "49_49") (pintype "passive"))
      (node (ref "U1") (pin "54") (pinfunction "PC4/DFSDM_CKIN2/I2S1_MCK/SPDIFRX_IN2/ETH_MII_RXD0/ETH_RMII_RXD0/FMC_SDNE0/ADC12_IN14_54") (pintype "passive"))
    )
    (net (code "117") (name "/PC5") (class "Default")
      (node (ref "J1") (pin "50") (pinfunction "50_50") (pintype "passive"))
      (node (ref "U1") (pin "55") (pinfunction "PC5/DFSDM_D2/SPDIFRX_IN3/ETH_MII_RXD1/ETH_RMII_RXD1/FMC_SDCKE0/ADC12_IN15_55") (pintype "passive"))
    )
    (net (code "118") (name "/PC10") (class "Default")
      (node (ref "J1") (pin "40") (pinfunction "40_40") (pintype "passive"))
      (node (ref "U1") (pin "139") (pinfunction "PC10/DFSDM_CKIN5/SPI3_SCK/I2S3_CK/U3_TX/U4_TX/QSPI_BK1_IO1/SDMMC1_D2/DCMI_D8/LCD_R2_139") (pintype "passive"))
    )
    (net (code "119") (name "/PC12") (class "Default")
      (node (ref "J1") (pin "38") (pinfunction "38_38") (pintype "passive"))
      (node (ref "U1") (pin "141") (pinfunction "PC12/SPI3_MOSI/I2S3_SD/U3_CK/U5_TX/SDMMC1_CK/DCMI_D9_141") (pintype "passive"))
    )
    (net (code "120") (name "/PD2") (class "Default")
      (node (ref "J1") (pin "37") (pinfunction "37_37") (pintype "passive"))
      (node (ref "U1") (pin "144") (pinfunction "PD2/TIM3_ETR/U5_RX/SDMMC1_CMD/DCMI_D11_144") (pintype "passive"))
    )
    (net (code "121") (name "/PE2") (class "Default")
      (node (ref "J1") (pin "20") (pinfunction "20_20") (pintype "passive"))
      (node (ref "U1") (pin "1") (pinfunction "PE2/SPI4_SCK/SAI1_MCLK_A/QSPI_BK1_IO2/ETH_MII_TXD3/FMC_A23_1") (pintype "passive"))
    )
    (net (code "122") (name "/PE3") (class "Default")
      (node (ref "J1") (pin "19") (pinfunction "19_19") (pintype "passive"))
      (node (ref "U1") (pin "2") (pinfunction "PE3/SAI1_SD_B/FMC_A19_2") (pintype "passive"))
    )
    (net (code "123") (name "/PE4") (class "Default")
      (node (ref "J1") (pin "18") (pinfunction "18_18") (pintype "passive"))
      (node (ref "U1") (pin "3") (pinfunction "PE4/DFSDM_D3/SPI4_NSS/SAI1_FS_A/FMC_A20/DCMI_D4/LCD_B0_3") (pintype "passive"))
    )
    (net (code "124") (name "/PE5") (class "Default")
      (node (ref "J1") (pin "17") (pinfunction "17_17") (pintype "passive"))
      (node (ref "U1") (pin "4") (pinfunction "PE5/DFSDM_CKIN3/TIM9_CH1/SPI4_MISO/SAI1_SCK_A/FMC_A21/DCMI_D6/LCD_G0_4") (pintype "passive"))
    )
    (net (code "125") (name "/PE6") (class "Default")
      (node (ref "J1") (pin "16") (pinfunction "16_16") (pintype "passive"))
      (node (ref "U1") (pin "5") (pinfunction "PE6/TIM1_BKIN2/TIM9_CH2/SPI4_MOSI/SAI1_SD_A/SAI2_MCK_B/FMC_A22/DCMI_D7/LCD_G1_5") (pintype "passive"))
    )
    (net (code "126") (name "/PF6") (class "Default")
      (node (ref "J1") (pin "14") (pinfunction "14_14") (pintype "passive"))
      (node (ref "U1") (pin "24") (pinfunction "PF6/TIM10_CH1/SPI5_NSS/SAI1_SD_B/U7_RX/QSPI_BK1_IO3/ADC3_IN4_24") (pintype "passive"))
    )
    (net (code "127") (name "/PF7") (class "Default")
      (node (ref "J1") (pin "13") (pinfunction "13_13") (pintype "passive"))
      (node (ref "U1") (pin "25") (pinfunction "PF7/TIM11_CH1/SPI5_SCK/SAI1_MCLK_B/U7_TX/QSPI_BK1_IO2/ADC3_IN5_25") (pintype "passive"))
    )
    (net (code "128") (name "/PF8") (class "Default")
      (node (ref "J1") (pin "12") (pinfunction "12_12") (pintype "passive"))
      (node (ref "U1") (pin "26") (pinfunction "PF8/TIM13_CH1/SPI5_MISO/SAI1_SCK_B/U7_RTS/QSPI_BK1_IO0/ADC3_IN6_26") (pintype "passive"))
    )
    (net (code "129") (name "/PF9") (class "Default")
      (node (ref "J1") (pin "11") (pinfunction "11_11") (pintype "passive"))
      (node (ref "U1") (pin "27") (pinfunction "PF9/TIM14_CH1/SPI5_MOSI/SAI1_FS_B/U7_CTS/QSPI_BK1_IO1/ADC3_IN7_27") (pintype "passive"))
    )
    (net (code "130") (name "/PG3") (class "Default")
      (node (ref "J2") (pin "13") (pinfunction "13_13") (pintype "passive"))
      (node (ref "U1") (pin "107") (pinfunction "PG3/FMC_A13_107") (pintype "passive"))
    )
    (net (code "131") (name "/PG13") (class "Default")
      (node (ref "J1") (pin "33") (pinfunction "33_33") (pintype "passive"))
      (node (ref "U1") (pin "156") (pinfunction "PG13/LPTIM1_OUT/SPI6_SCK/U6_CTS/ETH_MII_TXD0/ETH_RMII_TXD0/FMC_A24/LCD_R0_156") (pintype "passive"))
    )
    (net (code "132") (name "/PG14") (class "Default")
      (node (ref "J1") (pin "32") (pinfunction "32_32") (pintype "passive"))
      (node (ref "U1") (pin "157") (pinfunction "PG14/LPTIM1_ETR/SPI6_MOSI/U6_TX/QSPI_BK2_IO3/ETH_MII_TXD1/ETH_RMII_TXD1/FMC_A25/LCD_B0_157") (pintype "passive"))
    )
    (net (code "133") (name "/PH6") (class "Default")
      (node (ref "J2") (pin "8") (pinfunction "8_8") (pintype "passive"))
      (node (ref "U1") (pin "83") (pinfunction "PH6/I2C2_SMBA/SPI5_SCK/TIM12_CH1/ETH_MII_RXD2/FMC_SDNE1/DCMI_D8_83") (pintype "passive"))
    )
    (net (code "134") (name "/PH7") (class "Default")
      (node (ref "J2") (pin "9") (pinfunction "9_9") (pintype "passive"))
      (node (ref "U1") (pin "84") (pinfunction "PH7/I2C3_SCL/SPI5_MISO/ETH_MII_RXD3/FMC_SDCKE1/DCMI_D9_84") (pintype "passive"))
    )
    (net (code "135") (name "/PI3") (class "Default")
      (node (ref "J2") (pin "41") (pinfunction "41_41") (pintype "passive"))
      (node (ref "U1") (pin "134") (pinfunction "PI3/TIM8_ETR/SPI2_MOSI/I2S2_SD/FMC_D27/DCMI_D10_134") (pintype "passive"))
    )
    (net (code "136") (name "/PI8") (class "Default")
      (node (ref "J2") (pin "40") (pinfunction "40_40") (pintype "passive"))
      (node (ref "U1") (pin "7") (pinfunction "PI8/RTC_TAMP2/RTC_TS/WKUP5_7") (pintype "passive"))
    )
    (net (code "137") (name "/RESET") (class "Default")
      (node (ref "C12") (pin "1") (pintype "passive"))
      (node (ref "J1") (pin "10") (pinfunction "10_10") (pintype "passive"))
      (node (ref "P1") (pin "5") (pinfunction "5_5") (pintype "passive"))
      (node (ref "R6") (pin "1") (pintype "passive"))
      (node (ref "RST") (pin "1") (pinfunction "1_1") (pintype "passive"))
      (node (ref "U1") (pin "31") (pinfunction "NRST_31") (pintype "passive"))
    )
    (net (code "138") (name "/VBAT") (class "Default")
      (node (ref "D1") (pin "2") (pintype "passive"))
      (node (ref "J1") (pin "29") (pinfunction "29_29") (pintype "passive"))
    )
    (net (code "139") (name "/VCC5") (class "Default")
      (node (ref "J1") (pin "58") (pinfunction "58_58") (pintype "passive"))
      (node (ref "J1") (pin "59") (pinfunction "59_59") (pintype "passive"))
      (node (ref "J1") (pin "60") (pinfunction "60_60") (pintype "passive"))
    )
    (net (code "140") (name "/VREF+") (class "Default")
      (node (ref "J1") (pin "2") (pinfunction "2_2") (pintype "passive"))
    )
    (net (code "141") (name "GND") (class "Default")
      (node (ref "C1") (pin "2") (pintype "passive"))
      (node (ref "C10") (pin "1") (pintype "passive"))
      (node (ref "C11") (pin "1") (pintype "passive"))
      (node (ref "C12") (pin "2") (pintype "passive"))
      (node (ref "C13") (pin "1") (pintype "passive"))
      (node (ref "C14") (pin "1") (pintype "passive"))
      (node (ref "C15") (pin "1") (pintype "passive"))
      (node (ref "C16") (pin "1") (pintype "passive"))
      (node (ref "C17") (pin "1") (pintype "passive"))
      (node (ref "C18") (pin "1") (pintype "passive"))
      (node (ref "C19") (pin "1") (pintype "passive"))
      (node (ref "C2") (pin "1") (pintype "passive"))
      (node (ref "C20") (pin "1") (pintype "passive"))
      (node (ref "C21") (pin "1") (pintype "passive"))
      (node (ref "C22") (pin "1") (pintype "passive"))
      (node (ref "C23") (pin "1") (pintype "passive"))
      (node (ref "C24") (pin "1") (pintype "passive"))
      (node (ref "C25") (pin "1") (pintype "passive"))
      (node (ref "C26") (pin "1") (pintype "passive"))
      (node (ref "C27") (pin "1") (pintype "passive"))
      (node (ref "C3") (pin "2") (pintype "passive"))
      (node (ref "C4") (pin "1") (pintype "passive"))
      (node (ref "C5") (pin "2") (pintype "passive"))
      (node (ref "C6") (pin "1") (pintype "passive"))
      (node (ref "C7") (pin "1") (pintype "passive"))
      (node (ref "C8") (pin "1") (pintype "passive"))
      (node (ref "C9") (pin "1") (pintype "passive"))
      (node (ref "J1") (pin "1") (pinfunction "1_1") (pintype "passive"))
      (node (ref "J1") (pin "30") (pinfunction "30_30") (pintype "passive"))
      (node (ref "J2") (pin "31") (pinfunction "31_31") (pintype "passive"))
      (node (ref "P1") (pin "1") (pinfunction "1_1") (pintype "passive"))
      (node (ref "R1") (pin "2") (pintype "passive"))
      (node (ref "R4") (pin "2") (pintype "passive"))
      (node (ref "R7") (pin "2") (pintype "passive"))
      (node (ref "RST") (pin "2") (pinfunction "2_2") (pintype "passive"))
      (node (ref "U1") (pin "102") (pinfunction "VSS_102") (pintype "passive"))
      (node (ref "U1") (pin "113") (pinfunction "VSS_113") (pintype "passive"))
      (node (ref "U1") (pin "126") (pinfunction "VSS_126") (pintype "passive"))
      (node (ref "U1") (pin "135") (pinfunction "VSS_135") (pintype "passive"))
      (node (ref "U1") (pin "14") (pinfunction "VSS_14") (pintype "passive"))
      (node (ref "U1") (pin "148") (pinfunction "VSS_148") (pintype "passive"))
      (node (ref "U1") (pin "158") (pinfunction "VSS_158") (pintype "passive"))
      (node (ref "U1") (pin "22") (pinfunction "VSS_22") (pintype "passive"))
      (node (ref "U1") (pin "37") (pinfunction "VSSA_37") (pintype "passive"))
      (node (ref "U1") (pin "61") (pinfunction "VSS_61") (pintype "passive"))
      (node (ref "U1") (pin "71") (pinfunction "VSS_71") (pintype "passive"))
      (node (ref "U1") (pin "90") (pinfunction "VSS_90") (pintype "passive"))
      (node (ref "Y2") (pin "2") (pinfunction "GND_2") (pintype "passive"))
      (node (ref "Y2") (pin "4") (pinfunction "GND_4") (pintype "passive"))
    )
    (net (code "142") (name "Net-(U1-BYPASS_REG)") (class "Default")
      (node (ref "R1") (pin "1") (pintype "passive"))
      (node (ref "U1") (pin "48") (pinfunction "BYPASS_REG_48") (pintype "passive"))
    )
    (net (code "143") (name "Net-(U1-PC14{slash}OSC32_IN)") (class "Default")
      (node (ref "C8") (pin "2") (pintype "passive"))
      (node (ref "U1") (pin "9") (pinfunction "PC14/OSC32_IN_9") (pintype "passive"))
      (node (ref "Y1") (pin "1") (pinfunction "OSC1_1") (pintype "passive"))
    )
    (net (code "144") (name "Net-(U1-PC15{slash}OSC32_OUT)") (class "Default")
      (node (ref "C9") (pin "2") (pintype "passive"))
      (node (ref "U1") (pin "10") (pinfunction "PC15/OSC32_OUT_10") (pintype "passive"))
      (node (ref "Y1") (pin "2") (pinfunction "OSC2_2") (pintype "passive"))
    )
    (net (code "145") (name "Net-(U1-PDR_ON)") (class "Default")
      (node (ref "R4") (pin "1") (pintype "passive"))
      (node (ref "R5") (pin "1") (pintype "passive"))
      (node (ref "U1") (pin "171") (pinfunction "PDR_ON_171") (pintype "passive"))
    )
    (net (code "146") (name "Net-(U1-PH0{slash}OSC_IN)") (class "Default")
      (node (ref "C11") (pin "2") (pintype "passive"))
      (node (ref "U1") (pin "29") (pinfunction "PH0/OSC_IN_29") (pintype "passive"))
      (node (ref "Y2") (pin "3") (pinfunction "HOT_3") (pintype "passive"))
    )
    (net (code "147") (name "Net-(U1-PH1{slash}OSC_OUT)") (class "Default")
      (node (ref "C10") (pin "2") (pintype "passive"))
      (node (ref "U1") (pin "30") (pinfunction "PH1/OSC_OUT_30") (pintype "passive"))
      (node (ref "Y2") (pin "1") (pinfunction "HOT_1") (pintype "passive"))
    )
    (net (code "148") (name "Net-(U1-VBAT)") (class "Default")
      (node (ref "C1") (pin "1") (pintype "passive"))
      (node (ref "D1") (pin "3") (pintype "passive"))
      (node (ref "U1") (pin "6") (pinfunction "VBAT_6") (pintype "passive"))
    )
    (net (code "149") (name "Net-(U1-VCAP_1)") (class "Default")
      (node (ref "C3") (pin "1") (pintype "passive"))
      (node (ref "U1") (pin "81") (pinfunction "VCAP_1_81") (pintype "passive"))
    )
    (net (code "150") (name "Net-(U1-VCAP_2)") (class "Default")
      (node (ref "C5") (pin "1") (pintype "passive"))
      (node (ref "U1") (pin "125") (pinfunction "VCAP_2_125") (pintype "passive"))
    )
    (net (code "151") (name "Net-(U1-VREF+)") (class "Default")
      (node (ref "C2") (pin "2") (pintype "passive"))
      (node (ref "C4") (pin "2") (pintype "passive"))
      (node (ref "R2") (pin "1") (pintype "passive"))
      (node (ref "U1") (pin "38") (pinfunction "VREF+_38") (pintype "passive"))
    )
    (net (code "152") (name "VCC3.3") (class "Default")
      (node (ref "P1") (pin "4") (pinfunction "4_4") (pintype "passive"))
      (node (ref "R6") (pin "2") (pintype "passive"))
      (node (ref "R8") (pin "1") (pintype "passive"))
      (node (ref "R9") (pin "1") (pintype "passive"))
    )
    (net (code "153") (name "VCC3.3M") (class "Default")
      (node (ref "C13") (pin "2") (pintype "passive"))
      (node (ref "C14") (pin "2") (pintype "passive"))
      (node (ref "C15") (pin "2") (pintype "passive"))
      (node (ref "C16") (pin "2") (pintype "passive"))
      (node (ref "C17") (pin "2") (pintype "passive"))
      (node (ref "C18") (pin "2") (pintype "passive"))
      (node (ref "C19") (pin "2") (pintype "passive"))
      (node (ref "C20") (pin "2") (pintype "passive"))
      (node (ref "C21") (pin "2") (pintype "passive"))
      (node (ref "C22") (pin "2") (pintype "passive"))
      (node (ref "C23") (pin "2") (pintype "passive"))
      (node (ref "C24") (pin "2") (pintype "passive"))
      (node (ref "C25") (pin "2") (pintype "passive"))
      (node (ref "C26") (pin "2") (pintype "passive"))
      (node (ref "C27") (pin "2") (pintype "passive"))
      (node (ref "D1") (pin "1") (pintype "passive"))
      (node (ref "R3") (pin "2") (pintype "passive"))
      (node (ref "R5") (pin "2") (pintype "passive"))
      (node (ref "R8") (pin "2") (pintype "passive"))
      (node (ref "R9") (pin "2") (pintype "passive"))
      (node (ref "U1") (pin "103") (pinfunction "VDD_103") (pintype "passive"))
      (node (ref "U1") (pin "114") (pinfunction "VDD_114") (pintype "passive"))
      (node (ref "U1") (pin "127") (pinfunction "VDD_127") (pintype "passive"))
      (node (ref "U1") (pin "136") (pinfunction "VDD_136") (pintype "passive"))
      (node (ref "U1") (pin "149") (pinfunction "VDD_149") (pintype "passive"))
      (node (ref "U1") (pin "15") (pinfunction "VDD_15") (pintype "passive"))
      (node (ref "U1") (pin "159") (pinfunction "VDD_159") (pintype "passive"))
      (node (ref "U1") (pin "172") (pinfunction "VDD_172") (pintype "passive"))
      (node (ref "U1") (pin "23") (pinfunction "VDD_23") (pintype "passive"))
      (node (ref "U1") (pin "36") (pinfunction "VDD_36") (pintype "passive"))
      (node (ref "U1") (pin "49") (pinfunction "VDD_49") (pintype "passive"))
      (node (ref "U1") (pin "62") (pinfunction "VDD_62") (pintype "passive"))
      (node (ref "U1") (pin "72") (pinfunction "VDD_72") (pintype "passive"))
      (node (ref "U1") (pin "82") (pinfunction "VDD_82") (pintype "passive"))
      (node (ref "U1") (pin "91") (pinfunction "VDD_91") (pintype "passive"))
    )
    (net (code "154") (name "VDDA") (class "Default")
      (node (ref "C6") (pin "2") (pintype "passive"))
      (node (ref "C7") (pin "2") (pintype "passive"))
      (node (ref "R2") (pin "2") (pintype "passive"))
      (node (ref "R3") (pin "1") (pintype "passive"))
      (node (ref "U1") (pin "39") (pinfunction "VDDA_39") (pintype "passive"))
    )
  )
)
